# transmitter_with_ST7920_LCD.net
KiCad netlist of a schematic drawn in EAGLE
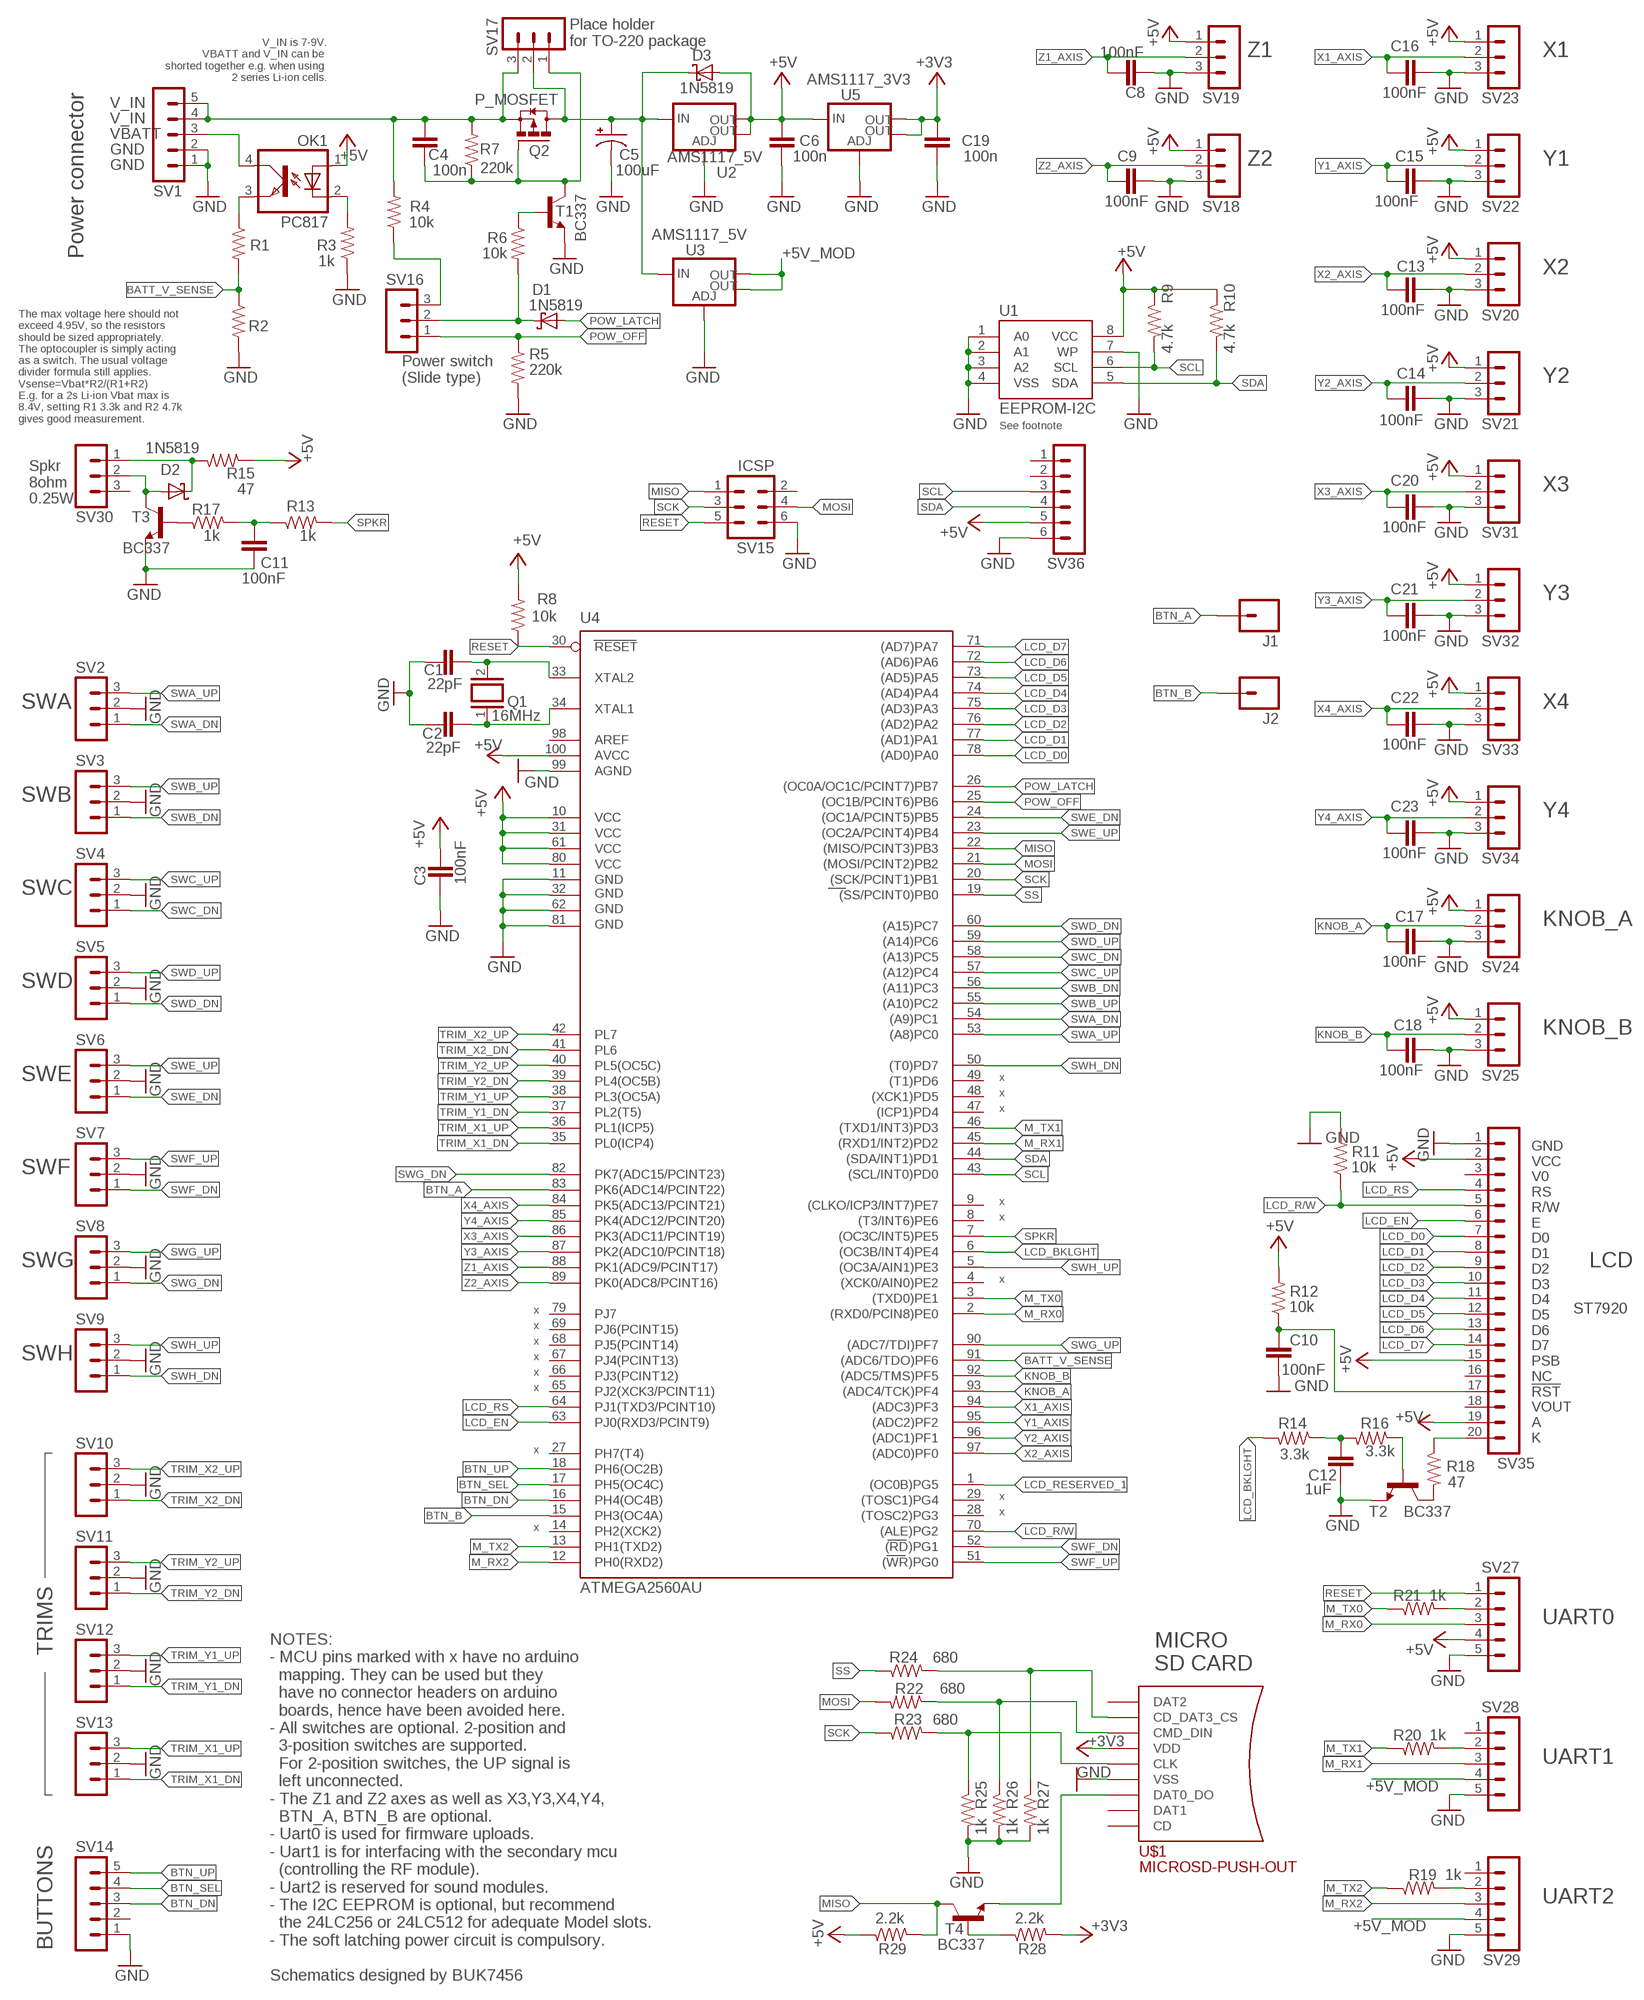
[diagram p0: schematic, sheet 1]

(export (version "E")
  (design (tool "Eeschema 10.0.6"))
  (components
    (comp (ref "C1")
      (value "22pF")
      (footprint "eagle-import:C050-024X044")
      (libsource (lib "eagle-import") (part "C-EU050-024X044"))
    )
    (comp (ref "C2")
      (value "22pF")
      (footprint "eagle-import:C050-024X044")
      (libsource (lib "eagle-import") (part "C-EU050-024X044"))
    )
    (comp (ref "C3")
      (value "100nF")
      (footprint "eagle-import:C050-024X044")
      (libsource (lib "eagle-import") (part "C-EU050-024X044"))
    )
    (comp (ref "C4")
      (value "100n")
      (footprint "eagle-import:C050-024X044")
      (libsource (lib "eagle-import") (part "C-EU050-024X044"))
    )
    (comp (ref "C5")
      (value "100uF")
      (footprint "eagle-import:E2,5-6E")
      (libsource (lib "eagle-import") (part "CPOL-USE2,5-6E"))
    )
    (comp (ref "C6")
      (value "100n")
      (footprint "eagle-import:C050-024X044")
      (libsource (lib "eagle-import") (part "C-EU050-024X044"))
    )
    (comp (ref "C8")
      (value "100nF")
      (footprint "eagle-import:C050-024X044")
      (libsource (lib "eagle-import") (part "C-EU050-024X044"))
    )
    (comp (ref "C9")
      (value "100nF")
      (footprint "eagle-import:C050-024X044")
      (libsource (lib "eagle-import") (part "C-EU050-024X044"))
    )
    (comp (ref "C10")
      (value "100nF")
      (footprint "eagle-import:C050-024X044")
      (libsource (lib "eagle-import") (part "C-EU050-024X044"))
    )
    (comp (ref "C11")
      (value "100nF")
      (footprint "eagle-import:C050-024X044")
      (libsource (lib "eagle-import") (part "C-EU050-024X044"))
    )
    (comp (ref "C12")
      (value "1uF")
      (footprint "eagle-import:C050-024X044")
      (libsource (lib "eagle-import") (part "C-EU050-024X044"))
    )
    (comp (ref "C13")
      (value "100nF")
      (footprint "eagle-import:C050-024X044")
      (libsource (lib "eagle-import") (part "C-EU050-024X044"))
    )
    (comp (ref "C14")
      (value "100nF")
      (footprint "eagle-import:C050-024X044")
      (libsource (lib "eagle-import") (part "C-EU050-024X044"))
    )
    (comp (ref "C15")
      (value "100nF")
      (footprint "eagle-import:C050-024X044")
      (libsource (lib "eagle-import") (part "C-EU050-024X044"))
    )
    (comp (ref "C16")
      (value "100nF")
      (footprint "eagle-import:C050-024X044")
      (libsource (lib "eagle-import") (part "C-EU050-024X044"))
    )
    (comp (ref "C17")
      (value "100nF")
      (footprint "eagle-import:C050-024X044")
      (libsource (lib "eagle-import") (part "C-EU050-024X044"))
    )
    (comp (ref "C18")
      (value "100nF")
      (footprint "eagle-import:C050-024X044")
      (libsource (lib "eagle-import") (part "C-EU050-024X044"))
    )
    (comp (ref "C19")
      (value "100n")
      (footprint "eagle-import:C050-024X044")
      (libsource (lib "eagle-import") (part "C-EU050-024X044"))
    )
    (comp (ref "C20")
      (value "100nF")
      (footprint "eagle-import:C050-024X044")
      (libsource (lib "eagle-import") (part "C-EU050-024X044"))
    )
    (comp (ref "C21")
      (value "100nF")
      (footprint "eagle-import:C050-024X044")
      (libsource (lib "eagle-import") (part "C-EU050-024X044"))
    )
    (comp (ref "C22")
      (value "100nF")
      (footprint "eagle-import:C050-024X044")
      (libsource (lib "eagle-import") (part "C-EU050-024X044"))
    )
    (comp (ref "C23")
      (value "100nF")
      (footprint "eagle-import:C050-024X044")
      (libsource (lib "eagle-import") (part "C-EU050-024X044"))
    )
    (comp (ref "D1")
      (value "1N5819")
      (footprint "eagle-import:DO41-7.6")
      (libsource (lib "eagle-import") (part "1N5817-B"))
    )
    (comp (ref "D2")
      (value "1N5819")
      (footprint "eagle-import:DO41-7.6")
      (libsource (lib "eagle-import") (part "1N5817-B"))
    )
    (comp (ref "D3")
      (value "1N5819")
      (footprint "eagle-import:DO41-7.6")
      (libsource (lib "eagle-import") (part "1N5817-B"))
    )
    (comp (ref "J1")
      (value "M01PTH_LONGPAD")
      (footprint "eagle-import:1X01_LONGPAD")
      (libsource (lib "eagle-import") (part "M01PTH_LONGPAD"))
    )
    (comp (ref "J2")
      (value "M01PTH_LONGPAD")
      (footprint "eagle-import:1X01_LONGPAD")
      (libsource (lib "eagle-import") (part "M01PTH_LONGPAD"))
    )
    (comp (ref "OK1")
      (value "PC817")
      (footprint "eagle-import:DIL04")
      (fields (field (name "MPN") "PC817X4J000F"))
      (libsource (lib "eagle-import") (part "PC817"))
    )
    (comp (ref "Q1")
      (value "16MHz")
      (footprint "eagle-import:QS")
      (libsource (lib "eagle-import") (part "XTAL/S"))
    )
    (comp (ref "Q2")
      (value "P_MOSFET")
      (footprint "eagle-import:SUPER-SOT3")
      (libsource (lib "eagle-import") (part "FDN360P"))
    )
    (comp (ref "R1")
      (value "1k")
      (footprint "eagle-import:0204_5")
      (libsource (lib "eagle-import") (part "R-US_0204/5"))
    )
    (comp (ref "R2")
      (value "1k")
      (footprint "eagle-import:0204_5")
      (libsource (lib "eagle-import") (part "R-US_0204/5"))
    )
    (comp (ref "R3")
      (value "1k")
      (footprint "eagle-import:0204_5")
      (libsource (lib "eagle-import") (part "R-US_0204/5"))
    )
    (comp (ref "R4")
      (value "10k")
      (footprint "eagle-import:0204_5")
      (libsource (lib "eagle-import") (part "R-US_0204/5"))
    )
    (comp (ref "R5")
      (value "220k")
      (footprint "eagle-import:0204_5")
      (libsource (lib "eagle-import") (part "R-US_0204/5"))
    )
    (comp (ref "R6")
      (value "10k")
      (footprint "eagle-import:0204_5")
      (libsource (lib "eagle-import") (part "R-US_0204/5"))
    )
    (comp (ref "R7")
      (value "220k")
      (footprint "eagle-import:0204_5")
      (libsource (lib "eagle-import") (part "R-US_0204/5"))
    )
    (comp (ref "R8")
      (value "10k")
      (footprint "eagle-import:0204_5")
      (libsource (lib "eagle-import") (part "R-US_0204/5"))
    )
    (comp (ref "R9")
      (value "4.7k")
      (footprint "eagle-import:0204_5")
      (libsource (lib "eagle-import") (part "R-US_0204/5"))
    )
    (comp (ref "R10")
      (value "4.7k")
      (footprint "eagle-import:0204_5")
      (libsource (lib "eagle-import") (part "R-US_0204/5"))
    )
    (comp (ref "R11")
      (value "10k")
      (footprint "eagle-import:0204_5")
      (libsource (lib "eagle-import") (part "resistor_R-US_0204/5"))
    )
    (comp (ref "R12")
      (value "10k")
      (footprint "eagle-import:0204_5")
      (libsource (lib "eagle-import") (part "resistor_R-US_0204/5"))
    )
    (comp (ref "R13")
      (value "1k")
      (footprint "eagle-import:0204_5")
      (libsource (lib "eagle-import") (part "R-US_0204/5"))
    )
    (comp (ref "R14")
      (value "3.3k")
      (footprint "eagle-import:0204_5")
      (libsource (lib "eagle-import") (part "R-US_0204/5"))
    )
    (comp (ref "R15")
      (value "47")
      (footprint "eagle-import:0204_5")
      (libsource (lib "eagle-import") (part "R-US_0204/5"))
    )
    (comp (ref "R16")
      (value "3.3k")
      (footprint "eagle-import:0204_5")
      (libsource (lib "eagle-import") (part "R-US_0204/5"))
    )
    (comp (ref "R17")
      (value "1k")
      (footprint "eagle-import:0204_5")
      (libsource (lib "eagle-import") (part "R-US_0204/5"))
    )
    (comp (ref "R18")
      (value "47")
      (footprint "eagle-import:0204_5")
      (libsource (lib "eagle-import") (part "R-US_0204/5"))
    )
    (comp (ref "R19")
      (value "1k")
      (footprint "eagle-import:0204_5")
      (libsource (lib "eagle-import") (part "R-US_0204/5"))
    )
    (comp (ref "R20")
      (value "1k")
      (footprint "eagle-import:0204_5")
      (libsource (lib "eagle-import") (part "R-US_0204/5"))
    )
    (comp (ref "R21")
      (value "1k")
      (footprint "eagle-import:0204_5")
      (libsource (lib "eagle-import") (part "R-US_0204/5"))
    )
    (comp (ref "R22")
      (value "680")
      (footprint "eagle-import:0204_5")
      (libsource (lib "eagle-import") (part "R-US_0204/5"))
    )
    (comp (ref "R23")
      (value "680")
      (footprint "eagle-import:0204_5")
      (libsource (lib "eagle-import") (part "R-US_0204/5"))
    )
    (comp (ref "R24")
      (value "680")
      (footprint "eagle-import:0204_5")
      (libsource (lib "eagle-import") (part "R-US_0204/5"))
    )
    (comp (ref "R25")
      (value "1k")
      (footprint "eagle-import:0204_5")
      (libsource (lib "eagle-import") (part "R-US_0204/5"))
    )
    (comp (ref "R26")
      (value "1k")
      (footprint "eagle-import:0204_5")
      (libsource (lib "eagle-import") (part "R-US_0204/5"))
    )
    (comp (ref "R27")
      (value "1k")
      (footprint "eagle-import:0204_5")
      (libsource (lib "eagle-import") (part "R-US_0204/5"))
    )
    (comp (ref "R28")
      (value "2.2k")
      (footprint "eagle-import:0204_5")
      (libsource (lib "eagle-import") (part "R-US_0204/5"))
    )
    (comp (ref "R29")
      (value "2.2k")
      (footprint "eagle-import:0204_5")
      (libsource (lib "eagle-import") (part "R-US_0204/5"))
    )
    (comp (ref "SV1")
      (value "MA05-1")
      (footprint "eagle-import:MA05-1")
      (libsource (lib "eagle-import") (part "MA05-1"))
    )
    (comp (ref "SV2")
      (value "MA03-1")
      (footprint "eagle-import:MA03-1")
      (libsource (lib "eagle-import") (part "MA03-1"))
    )
    (comp (ref "SV3")
      (value "MA03-1")
      (footprint "eagle-import:MA03-1")
      (libsource (lib "eagle-import") (part "MA03-1"))
    )
    (comp (ref "SV4")
      (value "MA03-1")
      (footprint "eagle-import:MA03-1")
      (libsource (lib "eagle-import") (part "MA03-1"))
    )
    (comp (ref "SV5")
      (value "MA03-1")
      (footprint "eagle-import:MA03-1")
      (libsource (lib "eagle-import") (part "MA03-1"))
    )
    (comp (ref "SV6")
      (value "MA03-1")
      (footprint "eagle-import:MA03-1")
      (libsource (lib "eagle-import") (part "MA03-1"))
    )
    (comp (ref "SV7")
      (value "MA03-1")
      (footprint "eagle-import:MA03-1")
      (libsource (lib "eagle-import") (part "MA03-1"))
    )
    (comp (ref "SV8")
      (value "MA03-1")
      (footprint "eagle-import:MA03-1")
      (libsource (lib "eagle-import") (part "MA03-1"))
    )
    (comp (ref "SV9")
      (value "MA03-1")
      (footprint "eagle-import:MA03-1")
      (libsource (lib "eagle-import") (part "MA03-1"))
    )
    (comp (ref "SV10")
      (value "MA03-1")
      (footprint "eagle-import:MA03-1")
      (libsource (lib "eagle-import") (part "MA03-1"))
    )
    (comp (ref "SV11")
      (value "MA03-1")
      (footprint "eagle-import:MA03-1")
      (libsource (lib "eagle-import") (part "MA03-1"))
    )
    (comp (ref "SV12")
      (value "MA03-1")
      (footprint "eagle-import:MA03-1")
      (libsource (lib "eagle-import") (part "MA03-1"))
    )
    (comp (ref "SV13")
      (value "MA03-1")
      (footprint "eagle-import:MA03-1")
      (libsource (lib "eagle-import") (part "MA03-1"))
    )
    (comp (ref "SV14")
      (value "MA05-1")
      (footprint "eagle-import:MA05-1")
      (libsource (lib "eagle-import") (part "MA05-1"))
    )
    (comp (ref "SV15")
      (value "ICSP")
      (footprint "eagle-import:MA03-2")
      (libsource (lib "eagle-import") (part "MA03-2"))
    )
    (comp (ref "SV16")
      (value "MA03-1")
      (footprint "eagle-import:MA03-1")
      (libsource (lib "eagle-import") (part "MA03-1"))
    )
    (comp (ref "SV17")
      (value "MA03-1")
      (footprint "eagle-import:MA03-1")
      (libsource (lib "eagle-import") (part "MA03-1"))
    )
    (comp (ref "SV18")
      (value "MA03-1")
      (footprint "eagle-import:MA03-1")
      (libsource (lib "eagle-import") (part "MA03-1"))
    )
    (comp (ref "SV19")
      (value "MA03-1")
      (footprint "eagle-import:MA03-1")
      (libsource (lib "eagle-import") (part "MA03-1"))
    )
    (comp (ref "SV20")
      (value "MA03-1")
      (footprint "eagle-import:MA03-1")
      (libsource (lib "eagle-import") (part "MA03-1"))
    )
    (comp (ref "SV21")
      (value "MA03-1")
      (footprint "eagle-import:MA03-1")
      (libsource (lib "eagle-import") (part "MA03-1"))
    )
    (comp (ref "SV22")
      (value "MA03-1")
      (footprint "eagle-import:MA03-1")
      (libsource (lib "eagle-import") (part "MA03-1"))
    )
    (comp (ref "SV23")
      (value "MA03-1")
      (footprint "eagle-import:MA03-1")
      (libsource (lib "eagle-import") (part "MA03-1"))
    )
    (comp (ref "SV24")
      (value "MA03-1")
      (footprint "eagle-import:MA03-1")
      (libsource (lib "eagle-import") (part "MA03-1"))
    )
    (comp (ref "SV25")
      (value "MA03-1")
      (footprint "eagle-import:MA03-1")
      (libsource (lib "eagle-import") (part "MA03-1"))
    )
    (comp (ref "SV27")
      (value "MA05-1")
      (footprint "eagle-import:MA05-1")
      (libsource (lib "eagle-import") (part "MA05-1"))
    )
    (comp (ref "SV28")
      (value "MA05-1")
      (footprint "eagle-import:MA05-1")
      (libsource (lib "eagle-import") (part "MA05-1"))
    )
    (comp (ref "SV29")
      (value "MA05-1")
      (footprint "eagle-import:MA05-1")
      (libsource (lib "eagle-import") (part "MA05-1"))
    )
    (comp (ref "SV30")
      (value "MA03-1")
      (footprint "eagle-import:MA03-1")
      (libsource (lib "eagle-import") (part "MA03-1"))
    )
    (comp (ref "SV31")
      (value "MA03-1")
      (footprint "eagle-import:MA03-1")
      (libsource (lib "eagle-import") (part "MA03-1"))
    )
    (comp (ref "SV32")
      (value "MA03-1")
      (footprint "eagle-import:MA03-1")
      (libsource (lib "eagle-import") (part "MA03-1"))
    )
    (comp (ref "SV33")
      (value "MA03-1")
      (footprint "eagle-import:MA03-1")
      (libsource (lib "eagle-import") (part "MA03-1"))
    )
    (comp (ref "SV34")
      (value "MA03-1")
      (footprint "eagle-import:MA03-1")
      (libsource (lib "eagle-import") (part "MA03-1"))
    )
    (comp (ref "SV35")
      (value "MA20-1")
      (footprint "eagle-import:MA20-1")
      (libsource (lib "eagle-import") (part "MA20-1"))
    )
    (comp (ref "SV36")
      (value "MA06-1")
      (footprint "eagle-import:MA06-1")
      (libsource (lib "eagle-import") (part "MA06-1"))
    )
    (comp (ref "T1")
      (value "BC337")
      (footprint "eagle-import:TO92")
      (libsource (lib "eagle-import") (part "BC337"))
    )
    (comp (ref "T2")
      (value "BC337")
      (footprint "eagle-import:TO92")
      (libsource (lib "eagle-import") (part "BC337"))
    )
    (comp (ref "T3")
      (value "BC337")
      (footprint "eagle-import:TO92")
      (libsource (lib "eagle-import") (part "BC337"))
    )
    (comp (ref "T4")
      (value "BC337")
      (footprint "eagle-import:TO92")
      (libsource (lib "eagle-import") (part "BC337"))
    )
    (comp (ref "U$1")
      (value "MICROSD-PUSH-OUT")
      (footprint "eagle-import:MICROSD-PUSH-OUT")
      (libsource (lib "eagle-import") (part "MICROSD-PUSH-OUT"))
    )
    (comp (ref "U1")
      (value "EEPROM-I2C")
      (footprint "eagle-import:SO08-EIAJ")
      (libsource (lib "eagle-import") (part "EEPROM-I2CEIAJ"))
    )
    (comp (ref "U2")
      (value "AMS1117_5V")
      (footprint "eagle-import:SOT223")
      (libsource (lib "eagle-import") (part "V_REG_LM1117SOT223"))
    )
    (comp (ref "U3")
      (value "AMS1117_5V")
      (footprint "eagle-import:SOT223")
      (libsource (lib "eagle-import") (part "V_REG_LM1117SOT223"))
    )
    (comp (ref "U4")
      (value "ATMEGA2560AU")
      (footprint "eagle-import:TQFP100")
      (libsource (lib "eagle-import") (part "ATMEGA2560AU"))
    )
    (comp (ref "U5")
      (value "AMS1117_3V3")
      (footprint "eagle-import:SOT223")
      (libsource (lib "eagle-import") (part "V_REG_LM1117SOT223"))
    )
  )
  (nets
    (net (code "1") (name "+3V3") (class "Default")
      (node (ref "C19") (pin "2") (pinfunction "2_2") (pintype "passive"))
      (node (ref "R28") (pin "2") (pinfunction "2_2") (pintype "passive"))
      (node (ref "U$1") (pin "4") (pinfunction "VDD_4") (pintype "bidirectional"))
      (node (ref "U5") (pin "2") (pinfunction "OUT_2") (pintype "output"))
      (node (ref "U5") (pin "4") (pinfunction "OUT_4") (pintype "output"))
    )
    (net (code "2") (name "+5V") (class "Default")
      (node (ref "C3") (pin "1") (pinfunction "1_1") (pintype "passive"))
      (node (ref "C6") (pin "2") (pinfunction "2_2") (pintype "passive"))
      (node (ref "D3") (pin "A") (pinfunction "A_A") (pintype "passive"))
      (node (ref "OK1") (pin "1") (pinfunction "A_1") (pintype "passive"))
      (node (ref "R10") (pin "1") (pinfunction "1_1") (pintype "passive"))
      (node (ref "R12") (pin "2") (pinfunction "2_2") (pintype "passive"))
      (node (ref "R15") (pin "1") (pinfunction "1_1") (pintype "passive"))
      (node (ref "R29") (pin "1") (pinfunction "1_1") (pintype "passive"))
      (node (ref "R8") (pin "2") (pinfunction "2_2") (pintype "passive"))
      (node (ref "R9") (pin "1") (pinfunction "1_1") (pintype "passive"))
      (node (ref "SV18") (pin "1") (pinfunction "1_1") (pintype "passive"))
      (node (ref "SV19") (pin "1") (pinfunction "1_1") (pintype "passive"))
      (node (ref "SV20") (pin "1") (pinfunction "1_1") (pintype "passive"))
      (node (ref "SV21") (pin "1") (pinfunction "1_1") (pintype "passive"))
      (node (ref "SV22") (pin "1") (pinfunction "1_1") (pintype "passive"))
      (node (ref "SV23") (pin "1") (pinfunction "1_1") (pintype "passive"))
      (node (ref "SV24") (pin "1") (pinfunction "1_1") (pintype "passive"))
      (node (ref "SV25") (pin "1") (pinfunction "1_1") (pintype "passive"))
      (node (ref "SV27") (pin "4") (pinfunction "4_4") (pintype "passive"))
      (node (ref "SV31") (pin "1") (pinfunction "1_1") (pintype "passive"))
      (node (ref "SV32") (pin "1") (pinfunction "1_1") (pintype "passive"))
      (node (ref "SV33") (pin "1") (pinfunction "1_1") (pintype "passive"))
      (node (ref "SV34") (pin "1") (pinfunction "1_1") (pintype "passive"))
      (node (ref "SV35") (pin "15") (pinfunction "15_15") (pintype "passive"))
      (node (ref "SV35") (pin "19") (pinfunction "19_19") (pintype "passive"))
      (node (ref "SV35") (pin "2") (pinfunction "2_2") (pintype "passive"))
      (node (ref "SV36") (pin "5") (pinfunction "5_5") (pintype "passive"))
      (node (ref "U1") (pin "8") (pinfunction "VCC_8") (pintype "power_in"))
      (node (ref "U2") (pin "2") (pinfunction "OUT_2") (pintype "output"))
      (node (ref "U2") (pin "4") (pinfunction "OUT_4") (pintype "output"))
      (node (ref "U4") (pin "10") (pinfunction "VCC_10") (pintype "power_in"))
      (node (ref "U4") (pin "100") (pinfunction "AVCC_100") (pintype "power_in"))
      (node (ref "U4") (pin "31") (pinfunction "VCC1_31") (pintype "power_in"))
      (node (ref "U4") (pin "61") (pinfunction "VCC2_61") (pintype "power_in"))
      (node (ref "U4") (pin "80") (pinfunction "VCC3_80") (pintype "power_in"))
      (node (ref "U5") (pin "3") (pinfunction "IN_3") (pintype "input"))
    )
    (net (code "3") (name "/+5V_MOD") (class "Default")
      (node (ref "SV28") (pin "4") (pinfunction "4_4") (pintype "passive"))
      (node (ref "SV29") (pin "4") (pinfunction "4_4") (pintype "passive"))
      (node (ref "U3") (pin "2") (pinfunction "OUT_2") (pintype "output"))
      (node (ref "U3") (pin "4") (pinfunction "OUT_4") (pintype "output"))
    )
    (net (code "4") (name "BATT_V_SENSE") (class "Default")
      (node (ref "R1") (pin "2") (pinfunction "2_2") (pintype "passive"))
      (node (ref "R2") (pin "1") (pinfunction "1_1") (pintype "passive"))
      (node (ref "U4") (pin "91") (pinfunction "(ADC6/TDO)PF6_91") (pintype "bidirectional"))
    )
    (net (code "5") (name "BTN_A") (class "Default")
      (node (ref "J1") (pin "1") (pinfunction "1_1") (pintype "passive"))
      (node (ref "U4") (pin "83") (pinfunction "PK6(ADC14/PCINT22)_83") (pintype "bidirectional"))
    )
    (net (code "6") (name "BTN_B") (class "Default")
      (node (ref "J2") (pin "1") (pinfunction "1_1") (pintype "passive"))
      (node (ref "U4") (pin "15") (pinfunction "PH3(OC4A)_15") (pintype "bidirectional"))
    )
    (net (code "7") (name "BTN_DN") (class "Default")
      (node (ref "SV14") (pin "3") (pinfunction "3_3") (pintype "passive"))
      (node (ref "U4") (pin "16") (pinfunction "PH4(OC4B)_16") (pintype "bidirectional"))
    )
    (net (code "8") (name "BTN_SEL") (class "Default")
      (node (ref "SV14") (pin "4") (pinfunction "4_4") (pintype "passive"))
      (node (ref "U4") (pin "17") (pinfunction "PH5(OC4C)_17") (pintype "bidirectional"))
    )
    (net (code "9") (name "BTN_UP") (class "Default")
      (node (ref "SV14") (pin "5") (pinfunction "5_5") (pintype "passive"))
      (node (ref "U4") (pin "18") (pinfunction "PH6(OC2B)_18") (pintype "bidirectional"))
    )
    (net (code "10") (name "GND") (class "Default")
      (node (ref "C1") (pin "1") (pinfunction "1_1") (pintype "passive"))
      (node (ref "C10") (pin "2") (pinfunction "2_2") (pintype "passive"))
      (node (ref "C11") (pin "2") (pinfunction "2_2") (pintype "passive"))
      (node (ref "C12") (pin "2") (pinfunction "2_2") (pintype "passive"))
      (node (ref "C13") (pin "1") (pinfunction "1_1") (pintype "passive"))
      (node (ref "C14") (pin "1") (pinfunction "1_1") (pintype "passive"))
      (node (ref "C15") (pin "1") (pinfunction "1_1") (pintype "passive"))
      (node (ref "C16") (pin "1") (pinfunction "1_1") (pintype "passive"))
      (node (ref "C17") (pin "1") (pinfunction "1_1") (pintype "passive"))
      (node (ref "C18") (pin "1") (pinfunction "1_1") (pintype "passive"))
      (node (ref "C19") (pin "1") (pinfunction "1_1") (pintype "passive"))
      (node (ref "C2") (pin "1") (pinfunction "1_1") (pintype "passive"))
      (node (ref "C20") (pin "1") (pinfunction "1_1") (pintype "passive"))
      (node (ref "C21") (pin "1") (pinfunction "1_1") (pintype "passive"))
      (node (ref "C22") (pin "1") (pinfunction "1_1") (pintype "passive"))
      (node (ref "C23") (pin "1") (pinfunction "1_1") (pintype "passive"))
      (node (ref "C3") (pin "2") (pinfunction "2_2") (pintype "passive"))
      (node (ref "C5") (pin "-") (pinfunction "-_-") (pintype "passive"))
      (node (ref "C6") (pin "1") (pinfunction "1_1") (pintype "passive"))
      (node (ref "C8") (pin "2") (pinfunction "2_2") (pintype "passive"))
      (node (ref "C9") (pin "1") (pinfunction "1_1") (pintype "passive"))
      (node (ref "R11") (pin "2") (pinfunction "2_2") (pintype "passive"))
      (node (ref "R2") (pin "2") (pinfunction "2_2") (pintype "passive"))
      (node (ref "R25") (pin "2") (pinfunction "2_2") (pintype "passive"))
      (node (ref "R26") (pin "2") (pinfunction "2_2") (pintype "passive"))
      (node (ref "R27") (pin "2") (pinfunction "2_2") (pintype "passive"))
      (node (ref "R3") (pin "1") (pinfunction "1_1") (pintype "passive"))
      (node (ref "R5") (pin "2") (pinfunction "2_2") (pintype "passive"))
      (node (ref "SV1") (pin "1") (pinfunction "1_1") (pintype "passive"))
      (node (ref "SV1") (pin "2") (pinfunction "2_2") (pintype "passive"))
      (node (ref "SV10") (pin "2") (pinfunction "2_2") (pintype "passive"))
      (node (ref "SV11") (pin "2") (pinfunction "2_2") (pintype "passive"))
      (node (ref "SV12") (pin "2") (pinfunction "2_2") (pintype "passive"))
      (node (ref "SV13") (pin "2") (pinfunction "2_2") (pintype "passive"))
      (node (ref "SV14") (pin "1") (pinfunction "1_1") (pintype "passive"))
      (node (ref "SV15") (pin "6") (pinfunction "6_6") (pintype "passive"))
      (node (ref "SV18") (pin "3") (pinfunction "3_3") (pintype "passive"))
      (node (ref "SV19") (pin "3") (pinfunction "3_3") (pintype "passive"))
      (node (ref "SV2") (pin "2") (pinfunction "2_2") (pintype "passive"))
      (node (ref "SV20") (pin "3") (pinfunction "3_3") (pintype "passive"))
      (node (ref "SV21") (pin "3") (pinfunction "3_3") (pintype "passive"))
      (node (ref "SV22") (pin "3") (pinfunction "3_3") (pintype "passive"))
      (node (ref "SV23") (pin "3") (pinfunction "3_3") (pintype "passive"))
      (node (ref "SV24") (pin "3") (pinfunction "3_3") (pintype "passive"))
      (node (ref "SV25") (pin "3") (pinfunction "3_3") (pintype "passive"))
      (node (ref "SV27") (pin "5") (pinfunction "5_5") (pintype "passive"))
      (node (ref "SV28") (pin "5") (pinfunction "5_5") (pintype "passive"))
      (node (ref "SV29") (pin "5") (pinfunction "5_5") (pintype "passive"))
      (node (ref "SV3") (pin "2") (pinfunction "2_2") (pintype "passive"))
      (node (ref "SV31") (pin "3") (pinfunction "3_3") (pintype "passive"))
      (node (ref "SV32") (pin "3") (pinfunction "3_3") (pintype "passive"))
      (node (ref "SV33") (pin "3") (pinfunction "3_3") (pintype "passive"))
      (node (ref "SV34") (pin "3") (pinfunction "3_3") (pintype "passive"))
      (node (ref "SV35") (pin "1") (pinfunction "1_1") (pintype "passive"))
      (node (ref "SV36") (pin "6") (pinfunction "6_6") (pintype "passive"))
      (node (ref "SV4") (pin "2") (pinfunction "2_2") (pintype "passive"))
      (node (ref "SV5") (pin "2") (pinfunction "2_2") (pintype "passive"))
      (node (ref "SV6") (pin "2") (pinfunction "2_2") (pintype "passive"))
      (node (ref "SV7") (pin "2") (pinfunction "2_2") (pintype "passive"))
      (node (ref "SV8") (pin "2") (pinfunction "2_2") (pintype "passive"))
      (node (ref "SV9") (pin "2") (pinfunction "2_2") (pintype "passive"))
      (node (ref "T1") (pin "1") (pinfunction "E_1") (pintype "passive"))
      (node (ref "T2") (pin "1") (pinfunction "E_1") (pintype "passive"))
      (node (ref "T3") (pin "1") (pinfunction "E_1") (pintype "passive"))
      (node (ref "U$1") (pin "6") (pinfunction "VSS_6") (pintype "bidirectional"))
      (node (ref "U$1") (pin "G1") (pinfunction "VSS_G1") (pintype "bidirectional"))
      (node (ref "U$1") (pin "G2") (pinfunction "VSS_G2") (pintype "bidirectional"))
      (node (ref "U$1") (pin "G3") (pinfunction "VSS_G3") (pintype "bidirectional"))
      (node (ref "U$1") (pin "G4") (pinfunction "VSS_G4") (pintype "bidirectional"))
      (node (ref "U1") (pin "1") (pinfunction "A0_1") (pintype "bidirectional"))
      (node (ref "U1") (pin "2") (pinfunction "A1_2") (pintype "bidirectional"))
      (node (ref "U1") (pin "3") (pinfunction "A2_3") (pintype "bidirectional"))
      (node (ref "U1") (pin "4") (pinfunction "VSS_4") (pintype "power_in"))
      (node (ref "U1") (pin "7") (pinfunction "WP_7") (pintype "bidirectional"))
      (node (ref "U2") (pin "1") (pinfunction "ADJ_1") (pintype "input"))
      (node (ref "U3") (pin "1") (pinfunction "ADJ_1") (pintype "input"))
      (node (ref "U4") (pin "11") (pinfunction "GND_11") (pintype "power_in"))
      (node (ref "U4") (pin "32") (pinfunction "GND1_32") (pintype "power_in"))
      (node (ref "U4") (pin "62") (pinfunction "GND2_62") (pintype "power_in"))
      (node (ref "U4") (pin "81") (pinfunction "GND3_81") (pintype "power_in"))
      (node (ref "U4") (pin "99") (pinfunction "AGND_99") (pintype "power_in"))
      (node (ref "U5") (pin "1") (pinfunction "ADJ_1") (pintype "input"))
    )
    (net (code "11") (name "KNOB_A") (class "Default")
      (node (ref "C17") (pin "2") (pinfunction "2_2") (pintype "passive"))
      (node (ref "SV24") (pin "2") (pinfunction "2_2") (pintype "passive"))
      (node (ref "U4") (pin "93") (pinfunction "(ADC4/TCK)PF4_93") (pintype "bidirectional"))
    )
    (net (code "12") (name "KNOB_B") (class "Default")
      (node (ref "C18") (pin "2") (pinfunction "2_2") (pintype "passive"))
      (node (ref "SV25") (pin "2") (pinfunction "2_2") (pintype "passive"))
      (node (ref "U4") (pin "92") (pinfunction "(ADC5/TMS)PF5_92") (pintype "bidirectional"))
    )
    (net (code "13") (name "LCD_BKLGHT") (class "Default")
      (node (ref "R14") (pin "2") (pinfunction "2_2") (pintype "passive"))
      (node (ref "U4") (pin "6") (pinfunction "(OC3B/INT4)PE4_6") (pintype "bidirectional"))
    )
    (net (code "14") (name "LCD_D0") (class "Default")
      (node (ref "SV35") (pin "7") (pinfunction "7_7") (pintype "passive"))
      (node (ref "U4") (pin "78") (pinfunction "(AD0)PA0_78") (pintype "bidirectional"))
    )
    (net (code "15") (name "LCD_D1") (class "Default")
      (node (ref "SV35") (pin "8") (pinfunction "8_8") (pintype "passive"))
      (node (ref "U4") (pin "77") (pinfunction "(AD1)PA1_77") (pintype "bidirectional"))
    )
    (net (code "16") (name "LCD_D2") (class "Default")
      (node (ref "SV35") (pin "9") (pinfunction "9_9") (pintype "passive"))
      (node (ref "U4") (pin "76") (pinfunction "(AD2)PA2_76") (pintype "bidirectional"))
    )
    (net (code "17") (name "LCD_D3") (class "Default")
      (node (ref "SV35") (pin "10") (pinfunction "10_10") (pintype "passive"))
      (node (ref "U4") (pin "75") (pinfunction "(AD3)PA3_75") (pintype "bidirectional"))
    )
    (net (code "18") (name "LCD_D4") (class "Default")
      (node (ref "SV35") (pin "11") (pinfunction "11_11") (pintype "passive"))
      (node (ref "U4") (pin "74") (pinfunction "(AD4)PA4_74") (pintype "bidirectional"))
    )
    (net (code "19") (name "LCD_D5") (class "Default")
      (node (ref "SV35") (pin "12") (pinfunction "12_12") (pintype "passive"))
      (node (ref "U4") (pin "73") (pinfunction "(AD5)PA5_73") (pintype "bidirectional"))
    )
    (net (code "20") (name "LCD_D6") (class "Default")
      (node (ref "SV35") (pin "13") (pinfunction "13_13") (pintype "passive"))
      (node (ref "U4") (pin "72") (pinfunction "(AD6)PA6_72") (pintype "bidirectional"))
    )
    (net (code "21") (name "LCD_D7") (class "Default")
      (node (ref "SV35") (pin "14") (pinfunction "14_14") (pintype "passive"))
      (node (ref "U4") (pin "71") (pinfunction "(AD7)PA7_71") (pintype "bidirectional"))
    )
    (net (code "22") (name "LCD_EN") (class "Default")
      (node (ref "SV35") (pin "6") (pinfunction "6_6") (pintype "passive"))
      (node (ref "U4") (pin "63") (pinfunction "PJ0(RXD3/PCINT9)_63") (pintype "bidirectional"))
    )
    (net (code "23") (name "LCD_RESERVED_1") (class "Default")
      (node (ref "U4") (pin "1") (pinfunction "(OC0B)PG5_1") (pintype "bidirectional"))
    )
    (net (code "24") (name "LCD_RS") (class "Default")
      (node (ref "SV35") (pin "4") (pinfunction "4_4") (pintype "passive"))
      (node (ref "U4") (pin "64") (pinfunction "PJ1(TXD3/PCINT10)_64") (pintype "bidirectional"))
    )
    (net (code "25") (name "LCD_R{slash}W") (class "Default")
      (node (ref "R11") (pin "1") (pinfunction "1_1") (pintype "passive"))
      (node (ref "SV35") (pin "5") (pinfunction "5_5") (pintype "passive"))
      (node (ref "U4") (pin "70") (pinfunction "(ALE)PG2_70") (pintype "bidirectional"))
    )
    (net (code "26") (name "MISO") (class "Default")
      (node (ref "R29") (pin "2") (pinfunction "2_2") (pintype "passive"))
      (node (ref "SV15") (pin "1") (pinfunction "1_1") (pintype "passive"))
      (node (ref "T4") (pin "3") (pinfunction "C_3") (pintype "passive"))
      (node (ref "U4") (pin "22") (pinfunction "(MISO/PCINT3)PB3_22") (pintype "bidirectional"))
    )
    (net (code "27") (name "MOSI") (class "Default")
      (node (ref "R22") (pin "2") (pinfunction "2_2") (pintype "passive"))
      (node (ref "SV15") (pin "4") (pinfunction "4_4") (pintype "passive"))
      (node (ref "U4") (pin "21") (pinfunction "(MOSI/PCINT2)PB2_21") (pintype "bidirectional"))
    )
    (net (code "28") (name "M_RX0") (class "Default")
      (node (ref "SV27") (pin "3") (pinfunction "3_3") (pintype "passive"))
      (node (ref "U4") (pin "2") (pinfunction "(RXD0/PCIN8)PE0_2") (pintype "bidirectional"))
    )
    (net (code "29") (name "M_RX1") (class "Default")
      (node (ref "SV28") (pin "3") (pinfunction "3_3") (pintype "passive"))
      (node (ref "U4") (pin "45") (pinfunction "(RXD1/INT2)PD2_45") (pintype "bidirectional"))
    )
    (net (code "30") (name "M_RX2") (class "Default")
      (node (ref "SV29") (pin "3") (pinfunction "3_3") (pintype "passive"))
      (node (ref "U4") (pin "12") (pinfunction "PH0(RXD2)_12") (pintype "bidirectional"))
    )
    (net (code "31") (name "M_TX0") (class "Default")
      (node (ref "R21") (pin "1") (pinfunction "1_1") (pintype "passive"))
      (node (ref "U4") (pin "3") (pinfunction "(TXD0)PE1_3") (pintype "bidirectional"))
    )
    (net (code "32") (name "M_TX1") (class "Default")
      (node (ref "R20") (pin "1") (pinfunction "1_1") (pintype "passive"))
      (node (ref "U4") (pin "46") (pinfunction "(TXD1/INT3)PD3_46") (pintype "bidirectional"))
    )
    (net (code "33") (name "M_TX2") (class "Default")
      (node (ref "R19") (pin "1") (pinfunction "1_1") (pintype "passive"))
      (node (ref "U4") (pin "13") (pinfunction "PH1(TXD2)_13") (pintype "bidirectional"))
    )
    (net (code "34") (name "Net-(C10-Pad1)") (class "Default")
      (node (ref "C10") (pin "1") (pinfunction "1_1") (pintype "passive"))
      (node (ref "R12") (pin "1") (pinfunction "1_1") (pintype "passive"))
      (node (ref "SV35") (pin "17") (pinfunction "17_17") (pintype "passive"))
    )
    (net (code "35") (name "Net-(C11-Pad1)") (class "Default")
      (node (ref "C11") (pin "1") (pinfunction "1_1") (pintype "passive"))
      (node (ref "R13") (pin "1") (pinfunction "1_1") (pintype "passive"))
      (node (ref "R17") (pin "2") (pinfunction "2_2") (pintype "passive"))
    )
    (net (code "36") (name "Net-(C12-Pad1)") (class "Default")
      (node (ref "C12") (pin "1") (pinfunction "1_1") (pintype "passive"))
      (node (ref "R14") (pin "1") (pinfunction "1_1") (pintype "passive"))
      (node (ref "R16") (pin "2") (pinfunction "2_2") (pintype "passive"))
    )
    (net (code "37") (name "Net-(D1-PadC)") (class "Default")
      (node (ref "D1") (pin "C") (pinfunction "C_C") (pintype "passive"))
      (node (ref "R6") (pin "2") (pinfunction "2_2") (pintype "passive"))
      (node (ref "SV16") (pin "2") (pinfunction "2_2") (pintype "passive"))
    )
    (net (code "38") (name "Net-(D2-PadC)") (class "Default")
      (node (ref "D2") (pin "C") (pinfunction "C_C") (pintype "passive"))
      (node (ref "R15") (pin "2") (pinfunction "2_2") (pintype "passive"))
      (node (ref "SV30") (pin "1") (pinfunction "1_1") (pintype "passive"))
    )
    (net (code "39") (name "Net-(OK1-C)") (class "Default")
      (node (ref "OK1") (pin "2") (pinfunction "C_2") (pintype "passive"))
      (node (ref "R3") (pin "2") (pinfunction "2_2") (pintype "passive"))
    )
    (net (code "40") (name "Net-(OK1-COL)") (class "Default")
      (node (ref "OK1") (pin "4") (pinfunction "COL_4") (pintype "passive"))
      (node (ref "SV1") (pin "3") (pinfunction "3_3") (pintype "passive"))
    )
    (net (code "41") (name "Net-(OK1-EMIT)") (class "Default")
      (node (ref "OK1") (pin "3") (pinfunction "EMIT_3") (pintype "passive"))
      (node (ref "R1") (pin "1") (pinfunction "1_1") (pintype "passive"))
    )
    (net (code "42") (name "Net-(Q2-D)") (class "Default")
      (node (ref "C5") (pin "+") (pinfunction "+_+") (pintype "passive"))
      (node (ref "D3") (pin "C") (pinfunction "C_C") (pintype "passive"))
      (node (ref "Q2") (pin "3") (pinfunction "D_3") (pintype "passive"))
      (node (ref "SV17") (pin "2") (pinfunction "2_2") (pintype "passive"))
      (node (ref "U2") (pin "3") (pinfunction "IN_3") (pintype "input"))
      (node (ref "U3") (pin "3") (pinfunction "IN_3") (pintype "input"))
    )
    (net (code "43") (name "Net-(Q2-G)") (class "Default")
      (node (ref "C4") (pin "1") (pinfunction "1_1") (pintype "passive"))
      (node (ref "Q2") (pin "1") (pinfunction "G_1") (pintype "passive"))
      (node (ref "R7") (pin "1") (pinfunction "1_1") (pintype "passive"))
      (node (ref "SV17") (pin "1") (pinfunction "1_1") (pintype "passive"))
      (node (ref "T1") (pin "3") (pinfunction "C_3") (pintype "passive"))
    )
    (net (code "44") (name "Net-(Q2-S)") (class "Default")
      (node (ref "C4") (pin "2") (pinfunction "2_2") (pintype "passive"))
      (node (ref "Q2") (pin "2") (pinfunction "S_2") (pintype "passive"))
      (node (ref "R4") (pin "2") (pinfunction "2_2") (pintype "passive"))
      (node (ref "R7") (pin "2") (pinfunction "2_2") (pintype "passive"))
      (node (ref "SV1") (pin "4") (pinfunction "4_4") (pintype "passive"))
      (node (ref "SV1") (pin "5") (pinfunction "5_5") (pintype "passive"))
      (node (ref "SV17") (pin "3") (pinfunction "3_3") (pintype "passive"))
    )
    (net (code "45") (name "Net-(R4-Pad1)") (class "Default")
      (node (ref "R4") (pin "1") (pinfunction "1_1") (pintype "passive"))
      (node (ref "SV16") (pin "3") (pinfunction "3_3") (pintype "passive"))
    )
    (net (code "46") (name "Net-(R18-Pad1)") (class "Default")
      (node (ref "R18") (pin "1") (pinfunction "1_1") (pintype "passive"))
      (node (ref "SV35") (pin "20") (pinfunction "20_20") (pintype "passive"))
    )
    (net (code "47") (name "Net-(R19-Pad2)") (class "Default")
      (node (ref "R19") (pin "2") (pinfunction "2_2") (pintype "passive"))
      (node (ref "SV29") (pin "2") (pinfunction "2_2") (pintype "passive"))
    )
    (net (code "48") (name "Net-(R20-Pad2)") (class "Default")
      (node (ref "R20") (pin "2") (pinfunction "2_2") (pintype "passive"))
      (node (ref "SV28") (pin "2") (pinfunction "2_2") (pintype "passive"))
    )
    (net (code "49") (name "Net-(R21-Pad2)") (class "Default")
      (node (ref "R21") (pin "2") (pinfunction "2_2") (pintype "passive"))
      (node (ref "SV27") (pin "2") (pinfunction "2_2") (pintype "passive"))
    )
    (net (code "50") (name "Net-(T1-B)") (class "Default")
      (node (ref "R6") (pin "1") (pinfunction "1_1") (pintype "passive"))
      (node (ref "T1") (pin "2") (pinfunction "B_2") (pintype "passive"))
    )
    (net (code "51") (name "Net-(T2-B)") (class "Default")
      (node (ref "R16") (pin "1") (pinfunction "1_1") (pintype "passive"))
      (node (ref "T2") (pin "2") (pinfunction "B_2") (pintype "passive"))
    )
    (net (code "52") (name "Net-(T2-C)") (class "Default")
      (node (ref "R18") (pin "2") (pinfunction "2_2") (pintype "passive"))
      (node (ref "T2") (pin "3") (pinfunction "C_3") (pintype "passive"))
    )
    (net (code "53") (name "Net-(T3-B)") (class "Default")
      (node (ref "R17") (pin "1") (pinfunction "1_1") (pintype "passive"))
      (node (ref "T3") (pin "2") (pinfunction "B_2") (pintype "passive"))
    )
    (net (code "54") (name "Net-(T3-C)") (class "Default")
      (node (ref "D2") (pin "A") (pinfunction "A_A") (pintype "passive"))
      (node (ref "SV30") (pin "2") (pinfunction "2_2") (pintype "passive"))
      (node (ref "T3") (pin "3") (pinfunction "C_3") (pintype "passive"))
    )
    (net (code "55") (name "Net-(T4-B)") (class "Default")
      (node (ref "R28") (pin "1") (pinfunction "1_1") (pintype "passive"))
      (node (ref "T4") (pin "2") (pinfunction "B_2") (pintype "passive"))
    )
    (net (code "56") (name "Net-(T4-E)") (class "Default")
      (node (ref "T4") (pin "1") (pinfunction "E_1") (pintype "passive"))
      (node (ref "U$1") (pin "7") (pinfunction "DAT0_DO_7") (pintype "bidirectional"))
    )
    (net (code "57") (name "Net-(U$1-CD_DAT3_CS)") (class "Default")
      (node (ref "R24") (pin "2") (pinfunction "2_2") (pintype "passive"))
      (node (ref "R27") (pin "1") (pinfunction "1_1") (pintype "passive"))
      (node (ref "U$1") (pin "2") (pinfunction "CD_DAT3_CS_2") (pintype "bidirectional"))
    )
    (net (code "58") (name "Net-(U$1-CLK)") (class "Default")
      (node (ref "R23") (pin "2") (pinfunction "2_2") (pintype "passive"))
      (node (ref "R25") (pin "1") (pinfunction "1_1") (pintype "passive"))
      (node (ref "U$1") (pin "5") (pinfunction "CLK_5") (pintype "bidirectional"))
    )
    (net (code "59") (name "Net-(U$1-CMD_DIN)") (class "Default")
      (node (ref "R22") (pin "1") (pinfunction "1_1") (pintype "passive"))
      (node (ref "R26") (pin "1") (pinfunction "1_1") (pintype "passive"))
      (node (ref "U$1") (pin "3") (pinfunction "CMD_DIN_3") (pintype "bidirectional"))
    )
    (net (code "60") (name "Net-(U4-XTAL1)") (class "Default")
      (node (ref "C2") (pin "2") (pinfunction "2_2") (pintype "passive"))
      (node (ref "Q1") (pin "1") (pinfunction "1_1") (pintype "passive"))
      (node (ref "U4") (pin "34") (pinfunction "XTAL1_34") (pintype "input"))
    )
    (net (code "61") (name "Net-(U4-XTAL2)") (class "Default")
      (node (ref "C1") (pin "2") (pinfunction "2_2") (pintype "passive"))
      (node (ref "Q1") (pin "2") (pinfunction "2_2") (pintype "passive"))
      (node (ref "U4") (pin "33") (pinfunction "XTAL2_33") (pintype "output"))
    )
    (net (code "62") (name "POW_LATCH") (class "Default")
      (node (ref "D1") (pin "A") (pinfunction "A_A") (pintype "passive"))
      (node (ref "U4") (pin "26") (pinfunction "(OC0A/OC1C/PCINT7)PB7_26") (pintype "bidirectional"))
    )
    (net (code "63") (name "POW_OFF") (class "Default")
      (node (ref "R5") (pin "1") (pinfunction "1_1") (pintype "passive"))
      (node (ref "SV16") (pin "1") (pinfunction "1_1") (pintype "passive"))
      (node (ref "U4") (pin "25") (pinfunction "(OC1B/PCINT6)PB6_25") (pintype "bidirectional"))
    )
    (net (code "64") (name "RESET") (class "Default")
      (node (ref "R8") (pin "1") (pinfunction "1_1") (pintype "passive"))
      (node (ref "SV15") (pin "5") (pinfunction "5_5") (pintype "passive"))
      (node (ref "SV27") (pin "1") (pinfunction "1_1") (pintype "passive"))
      (node (ref "U4") (pin "30") (pinfunction "RESET_30") (pintype "input"))
    )
    (net (code "65") (name "SCK") (class "Default")
      (node (ref "R23") (pin "1") (pinfunction "1_1") (pintype "passive"))
      (node (ref "SV15") (pin "3") (pinfunction "3_3") (pintype "passive"))
      (node (ref "U4") (pin "20") (pinfunction "(SCK/PCINT1)PB1_20") (pintype "bidirectional"))
    )
    (net (code "66") (name "SCL") (class "Default")
      (node (ref "R9") (pin "2") (pinfunction "2_2") (pintype "passive"))
      (node (ref "SV36") (pin "3") (pinfunction "3_3") (pintype "passive"))
      (node (ref "U1") (pin "6") (pinfunction "SCL_6") (pintype "bidirectional"))
      (node (ref "U4") (pin "43") (pinfunction "(SCL/INT0)PD0_43") (pintype "bidirectional"))
    )
    (net (code "67") (name "SDA") (class "Default")
      (node (ref "R10") (pin "2") (pinfunction "2_2") (pintype "passive"))
      (node (ref "SV36") (pin "4") (pinfunction "4_4") (pintype "passive"))
      (node (ref "U1") (pin "5") (pinfunction "SDA_5") (pintype "bidirectional"))
      (node (ref "U4") (pin "44") (pinfunction "(SDA/INT1)PD1_44") (pintype "bidirectional"))
    )
    (net (code "68") (name "SPKR") (class "Default")
      (node (ref "R13") (pin "2") (pinfunction "2_2") (pintype "passive"))
      (node (ref "U4") (pin "7") (pinfunction "(OC3C/INT5)PE5_7") (pintype "bidirectional"))
    )
    (net (code "69") (name "SS") (class "Default")
      (node (ref "R24") (pin "1") (pinfunction "1_1") (pintype "passive"))
      (node (ref "U4") (pin "19") (pinfunction "(SS/PCINT0)PB0_19") (pintype "bidirectional"))
    )
    (net (code "70") (name "SWA_DN") (class "Default")
      (node (ref "SV2") (pin "1") (pinfunction "1_1") (pintype "passive"))
      (node (ref "U4") (pin "54") (pinfunction "(A9)PC1_54") (pintype "bidirectional"))
    )
    (net (code "71") (name "SWA_UP") (class "Default")
      (node (ref "SV2") (pin "3") (pinfunction "3_3") (pintype "passive"))
      (node (ref "U4") (pin "53") (pinfunction "(A8)PC0_53") (pintype "bidirectional"))
    )
    (net (code "72") (name "SWB_DN") (class "Default")
      (node (ref "SV3") (pin "1") (pinfunction "1_1") (pintype "passive"))
      (node (ref "U4") (pin "56") (pinfunction "(A11)PC3_56") (pintype "bidirectional"))
    )
    (net (code "73") (name "SWB_UP") (class "Default")
      (node (ref "SV3") (pin "3") (pinfunction "3_3") (pintype "passive"))
      (node (ref "U4") (pin "55") (pinfunction "(A10)PC2_55") (pintype "bidirectional"))
    )
    (net (code "74") (name "SWC_DN") (class "Default")
      (node (ref "SV4") (pin "1") (pinfunction "1_1") (pintype "passive"))
      (node (ref "U4") (pin "58") (pinfunction "(A13)PC5_58") (pintype "bidirectional"))
    )
    (net (code "75") (name "SWC_UP") (class "Default")
      (node (ref "SV4") (pin "3") (pinfunction "3_3") (pintype "passive"))
      (node (ref "U4") (pin "57") (pinfunction "(A12)PC4_57") (pintype "bidirectional"))
    )
    (net (code "76") (name "SWD_DN") (class "Default")
      (node (ref "SV5") (pin "1") (pinfunction "1_1") (pintype "passive"))
      (node (ref "U4") (pin "60") (pinfunction "(A15)PC7_60") (pintype "bidirectional"))
    )
    (net (code "77") (name "SWD_UP") (class "Default")
      (node (ref "SV5") (pin "3") (pinfunction "3_3") (pintype "passive"))
      (node (ref "U4") (pin "59") (pinfunction "(A14)PC6_59") (pintype "bidirectional"))
    )
    (net (code "78") (name "SWE_DN") (class "Default")
      (node (ref "SV6") (pin "1") (pinfunction "1_1") (pintype "passive"))
      (node (ref "U4") (pin "24") (pinfunction "(OC1A/PCINT5)PB5_24") (pintype "bidirectional"))
    )
    (net (code "79") (name "SWE_UP") (class "Default")
      (node (ref "SV6") (pin "3") (pinfunction "3_3") (pintype "passive"))
      (node (ref "U4") (pin "23") (pinfunction "(OC2A/PCINT4)PB4_23") (pintype "bidirectional"))
    )
    (net (code "80") (name "SWF_DN") (class "Default")
      (node (ref "SV7") (pin "1") (pinfunction "1_1") (pintype "passive"))
      (node (ref "U4") (pin "52") (pinfunction "(RD)PG1_52") (pintype "bidirectional"))
    )
    (net (code "81") (name "SWF_UP") (class "Default")
      (node (ref "SV7") (pin "3") (pinfunction "3_3") (pintype "passive"))
      (node (ref "U4") (pin "51") (pinfunction "(WR)PG0_51") (pintype "bidirectional"))
    )
    (net (code "82") (name "SWG_DN") (class "Default")
      (node (ref "SV8") (pin "1") (pinfunction "1_1") (pintype "passive"))
      (node (ref "U4") (pin "82") (pinfunction "PK7(ADC15/PCINT23)_82") (pintype "bidirectional"))
    )
    (net (code "83") (name "SWG_UP") (class "Default")
      (node (ref "SV8") (pin "3") (pinfunction "3_3") (pintype "passive"))
      (node (ref "U4") (pin "90") (pinfunction "(ADC7/TDI)PF7_90") (pintype "bidirectional"))
    )
    (net (code "84") (name "SWH_DN") (class "Default")
      (node (ref "SV9") (pin "1") (pinfunction "1_1") (pintype "passive"))
      (node (ref "U4") (pin "50") (pinfunction "(T0)PD7_50") (pintype "bidirectional"))
    )
    (net (code "85") (name "SWH_UP") (class "Default")
      (node (ref "SV9") (pin "3") (pinfunction "3_3") (pintype "passive"))
      (node (ref "U4") (pin "5") (pinfunction "(OC3A/AIN1)PE3_5") (pintype "bidirectional"))
    )
    (net (code "86") (name "TRIM_X1_DN") (class "Default")
      (node (ref "SV13") (pin "1") (pinfunction "1_1") (pintype "passive"))
      (node (ref "U4") (pin "35") (pinfunction "PL0(ICP4)_35") (pintype "bidirectional"))
    )
    (net (code "87") (name "TRIM_X1_UP") (class "Default")
      (node (ref "SV13") (pin "3") (pinfunction "3_3") (pintype "passive"))
      (node (ref "U4") (pin "36") (pinfunction "PL1(ICP5)_36") (pintype "bidirectional"))
    )
    (net (code "88") (name "TRIM_X2_DN") (class "Default")
      (node (ref "SV10") (pin "1") (pinfunction "1_1") (pintype "passive"))
      (node (ref "U4") (pin "41") (pinfunction "PL6_41") (pintype "bidirectional"))
    )
    (net (code "89") (name "TRIM_X2_UP") (class "Default")
      (node (ref "SV10") (pin "3") (pinfunction "3_3") (pintype "passive"))
      (node (ref "U4") (pin "42") (pinfunction "PL7_42") (pintype "bidirectional"))
    )
    (net (code "90") (name "TRIM_Y1_DN") (class "Default")
      (node (ref "SV12") (pin "1") (pinfunction "1_1") (pintype "passive"))
      (node (ref "U4") (pin "37") (pinfunction "PL2(T5)_37") (pintype "bidirectional"))
    )
    (net (code "91") (name "TRIM_Y1_UP") (class "Default")
      (node (ref "SV12") (pin "3") (pinfunction "3_3") (pintype "passive"))
      (node (ref "U4") (pin "38") (pinfunction "PL3(OC5A)_38") (pintype "bidirectional"))
    )
    (net (code "92") (name "TRIM_Y2_DN") (class "Default")
      (node (ref "SV11") (pin "1") (pinfunction "1_1") (pintype "passive"))
      (node (ref "U4") (pin "39") (pinfunction "PL4(OC5B)_39") (pintype "bidirectional"))
    )
    (net (code "93") (name "TRIM_Y2_UP") (class "Default")
      (node (ref "SV11") (pin "3") (pinfunction "3_3") (pintype "passive"))
      (node (ref "U4") (pin "40") (pinfunction "PL5(OC5C)_40") (pintype "bidirectional"))
    )
    (net (code "94") (name "X1_AXIS") (class "Default")
      (node (ref "C16") (pin "2") (pinfunction "2_2") (pintype "passive"))
      (node (ref "SV23") (pin "2") (pinfunction "2_2") (pintype "passive"))
      (node (ref "U4") (pin "94") (pinfunction "(ADC3)PF3_94") (pintype "bidirectional"))
    )
    (net (code "95") (name "X2_AXIS") (class "Default")
      (node (ref "C13") (pin "2") (pinfunction "2_2") (pintype "passive"))
      (node (ref "SV20") (pin "2") (pinfunction "2_2") (pintype "passive"))
      (node (ref "U4") (pin "97") (pinfunction "(ADC0)PF0_97") (pintype "bidirectional"))
    )
    (net (code "96") (name "X3_AXIS") (class "Default")
      (node (ref "C20") (pin "2") (pinfunction "2_2") (pintype "passive"))
      (node (ref "SV31") (pin "2") (pinfunction "2_2") (pintype "passive"))
      (node (ref "U4") (pin "86") (pinfunction "PK3(ADC11/PCINT19)_86") (pintype "bidirectional"))
    )
    (net (code "97") (name "X4_AXIS") (class "Default")
      (node (ref "C22") (pin "2") (pinfunction "2_2") (pintype "passive"))
      (node (ref "SV33") (pin "2") (pinfunction "2_2") (pintype "passive"))
      (node (ref "U4") (pin "84") (pinfunction "PK5(ADC13/PCINT21)_84") (pintype "bidirectional"))
    )
    (net (code "98") (name "Y1_AXIS") (class "Default")
      (node (ref "C15") (pin "2") (pinfunction "2_2") (pintype "passive"))
      (node (ref "SV22") (pin "2") (pinfunction "2_2") (pintype "passive"))
      (node (ref "U4") (pin "95") (pinfunction "(ADC2)PF2_95") (pintype "bidirectional"))
    )
    (net (code "99") (name "Y2_AXIS") (class "Default")
      (node (ref "C14") (pin "2") (pinfunction "2_2") (pintype "passive"))
      (node (ref "SV21") (pin "2") (pinfunction "2_2") (pintype "passive"))
      (node (ref "U4") (pin "96") (pinfunction "(ADC1)PF1_96") (pintype "bidirectional"))
    )
    (net (code "100") (name "Y3_AXIS") (class "Default")
      (node (ref "C21") (pin "2") (pinfunction "2_2") (pintype "passive"))
      (node (ref "SV32") (pin "2") (pinfunction "2_2") (pintype "passive"))
      (node (ref "U4") (pin "87") (pinfunction "PK2(ADC10/PCINT18)_87") (pintype "bidirectional"))
    )
    (net (code "101") (name "Y4_AXIS") (class "Default")
      (node (ref "C23") (pin "2") (pinfunction "2_2") (pintype "passive"))
      (node (ref "SV34") (pin "2") (pinfunction "2_2") (pintype "passive"))
      (node (ref "U4") (pin "85") (pinfunction "PK4(ADC12/PCINT20)_85") (pintype "bidirectional"))
    )
    (net (code "102") (name "Z1_AXIS") (class "Default")
      (node (ref "C8") (pin "1") (pinfunction "1_1") (pintype "passive"))
      (node (ref "SV19") (pin "2") (pinfunction "2_2") (pintype "passive"))
      (node (ref "U4") (pin "88") (pinfunction "PK1(ADC9/PCINT17)_88") (pintype "bidirectional"))
    )
    (net (code "103") (name "Z2_AXIS") (class "Default")
      (node (ref "C9") (pin "2") (pinfunction "2_2") (pintype "passive"))
      (node (ref "SV18") (pin "2") (pinfunction "2_2") (pintype "passive"))
      (node (ref "U4") (pin "89") (pinfunction "PK0(ADC8/PCINT16)_89") (pintype "bidirectional"))
    )
    (net (code "104") (name "unconnected-(SV14-Pad2)") (class "Default")
      (node (ref "SV14") (pin "2") (pinfunction "2_2") (pintype "passive"))
    )
    (net (code "105") (name "unconnected-(SV15-Pad2)") (class "Default")
      (node (ref "SV15") (pin "2") (pinfunction "2_2") (pintype "passive"))
    )
    (net (code "106") (name "unconnected-(SV28-Pad1)") (class "Default")
      (node (ref "SV28") (pin "1") (pinfunction "1_1") (pintype "passive"))
    )
    (net (code "107") (name "unconnected-(SV29-Pad1)") (class "Default")
      (node (ref "SV29") (pin "1") (pinfunction "1_1") (pintype "passive"))
    )
    (net (code "108") (name "unconnected-(SV30-Pad3)") (class "Default")
      (node (ref "SV30") (pin "3") (pinfunction "3_3") (pintype "passive"))
    )
    (net (code "109") (name "unconnected-(SV35-Pad3)") (class "Default")
      (node (ref "SV35") (pin "3") (pinfunction "3_3") (pintype "passive"))
    )
    (net (code "110") (name "unconnected-(SV35-Pad16)") (class "Default")
      (node (ref "SV35") (pin "16") (pinfunction "16_16") (pintype "passive"))
    )
    (net (code "111") (name "unconnected-(SV35-Pad18)") (class "Default")
      (node (ref "SV35") (pin "18") (pinfunction "18_18") (pintype "passive"))
    )
    (net (code "112") (name "unconnected-(SV36-Pad1)") (class "Default")
      (node (ref "SV36") (pin "1") (pinfunction "1_1") (pintype "passive"))
    )
    (net (code "113") (name "unconnected-(SV36-Pad2)") (class "Default")
      (node (ref "SV36") (pin "2") (pinfunction "2_2") (pintype "passive"))
    )
    (net (code "114") (name "unconnected-(U$1-DAT1-Pad8)") (class "Default")
      (node (ref "U$1") (pin "8") (pinfunction "DAT1_8") (pintype "bidirectional"))
    )
    (net (code "115") (name "unconnected-(U$1-DAT2-Pad1)") (class "Default")
      (node (ref "U$1") (pin "1") (pinfunction "DAT2_1") (pintype "bidirectional"))
    )
    (net (code "116") (name "unconnected-(U$1-PadCD)") (class "Default")
      (node (ref "U$1") (pin "CD") (pinfunction "CD_CD") (pintype "bidirectional"))
    )
    (net (code "117") (name "unconnected-(U4-(CLKO{slash}ICP3{slash}INT7)PE7-Pad9)") (class "Default")
      (node (ref "U4") (pin "9") (pinfunction "(CLKO/ICP3/INT7)PE7_9") (pintype "bidirectional"))
    )
    (net (code "118") (name "unconnected-(U4-(ICP1)PD4-Pad47)") (class "Default")
      (node (ref "U4") (pin "47") (pinfunction "(ICP1)PD4_47") (pintype "bidirectional"))
    )
    (net (code "119") (name "unconnected-(U4-(T1)PD6-Pad49)") (class "Default")
      (node (ref "U4") (pin "49") (pinfunction "(T1)PD6_49") (pintype "bidirectional"))
    )
    (net (code "120") (name "unconnected-(U4-(T3{slash}INT6)PE6-Pad8)") (class "Default")
      (node (ref "U4") (pin "8") (pinfunction "(T3/INT6)PE6_8") (pintype "bidirectional"))
    )
    (net (code "121") (name "unconnected-(U4-(TOSC1)PG4-Pad29)") (class "Default")
      (node (ref "U4") (pin "29") (pinfunction "(TOSC1)PG4_29") (pintype "bidirectional"))
    )
    (net (code "122") (name "unconnected-(U4-(TOSC2)PG3-Pad28)") (class "Default")
      (node (ref "U4") (pin "28") (pinfunction "(TOSC2)PG3_28") (pintype "bidirectional"))
    )
    (net (code "123") (name "unconnected-(U4-(XCK0{slash}AIN0)PE2-Pad4)") (class "Default")
      (node (ref "U4") (pin "4") (pinfunction "(XCK0/AIN0)PE2_4") (pintype "bidirectional"))
    )
    (net (code "124") (name "unconnected-(U4-(XCK1)PD5-Pad48)") (class "Default")
      (node (ref "U4") (pin "48") (pinfunction "(XCK1)PD5_48") (pintype "bidirectional"))
    )
    (net (code "125") (name "unconnected-(U4-AREF-Pad98)") (class "Default")
      (node (ref "U4") (pin "98") (pinfunction "AREF_98") (pintype "bidirectional"))
    )
    (net (code "126") (name "unconnected-(U4-PH2(XCK2)-Pad14)") (class "Default")
      (node (ref "U4") (pin "14") (pinfunction "PH2(XCK2)_14") (pintype "bidirectional"))
    )
    (net (code "127") (name "unconnected-(U4-PH7(T4)-Pad27)") (class "Default")
      (node (ref "U4") (pin "27") (pinfunction "PH7(T4)_27") (pintype "bidirectional"))
    )
    (net (code "128") (name "unconnected-(U4-PJ2(XCK3{slash}PCINT11)-Pad65)") (class "Default")
      (node (ref "U4") (pin "65") (pinfunction "PJ2(XCK3/PCINT11)_65") (pintype "bidirectional"))
    )
    (net (code "129") (name "unconnected-(U4-PJ3(PCINT12)-Pad66)") (class "Default")
      (node (ref "U4") (pin "66") (pinfunction "PJ3(PCINT12)_66") (pintype "bidirectional"))
    )
    (net (code "130") (name "unconnected-(U4-PJ4(PCINT13)-Pad67)") (class "Default")
      (node (ref "U4") (pin "67") (pinfunction "PJ4(PCINT13)_67") (pintype "bidirectional"))
    )
    (net (code "131") (name "unconnected-(U4-PJ5(PCINT14)-Pad68)") (class "Default")
      (node (ref "U4") (pin "68") (pinfunction "PJ5(PCINT14)_68") (pintype "bidirectional"))
    )
    (net (code "132") (name "unconnected-(U4-PJ6(PCINT15)-Pad69)") (class "Default")
      (node (ref "U4") (pin "69") (pinfunction "PJ6(PCINT15)_69") (pintype "bidirectional"))
    )
    (net (code "133") (name "unconnected-(U4-PJ7-Pad79)") (class "Default")
      (node (ref "U4") (pin "79") (pinfunction "PJ7_79") (pintype "bidirectional"))
    )
  )
)
